# Sheet1.net
KiCad netlist of a schematic drawn in Altium Designer
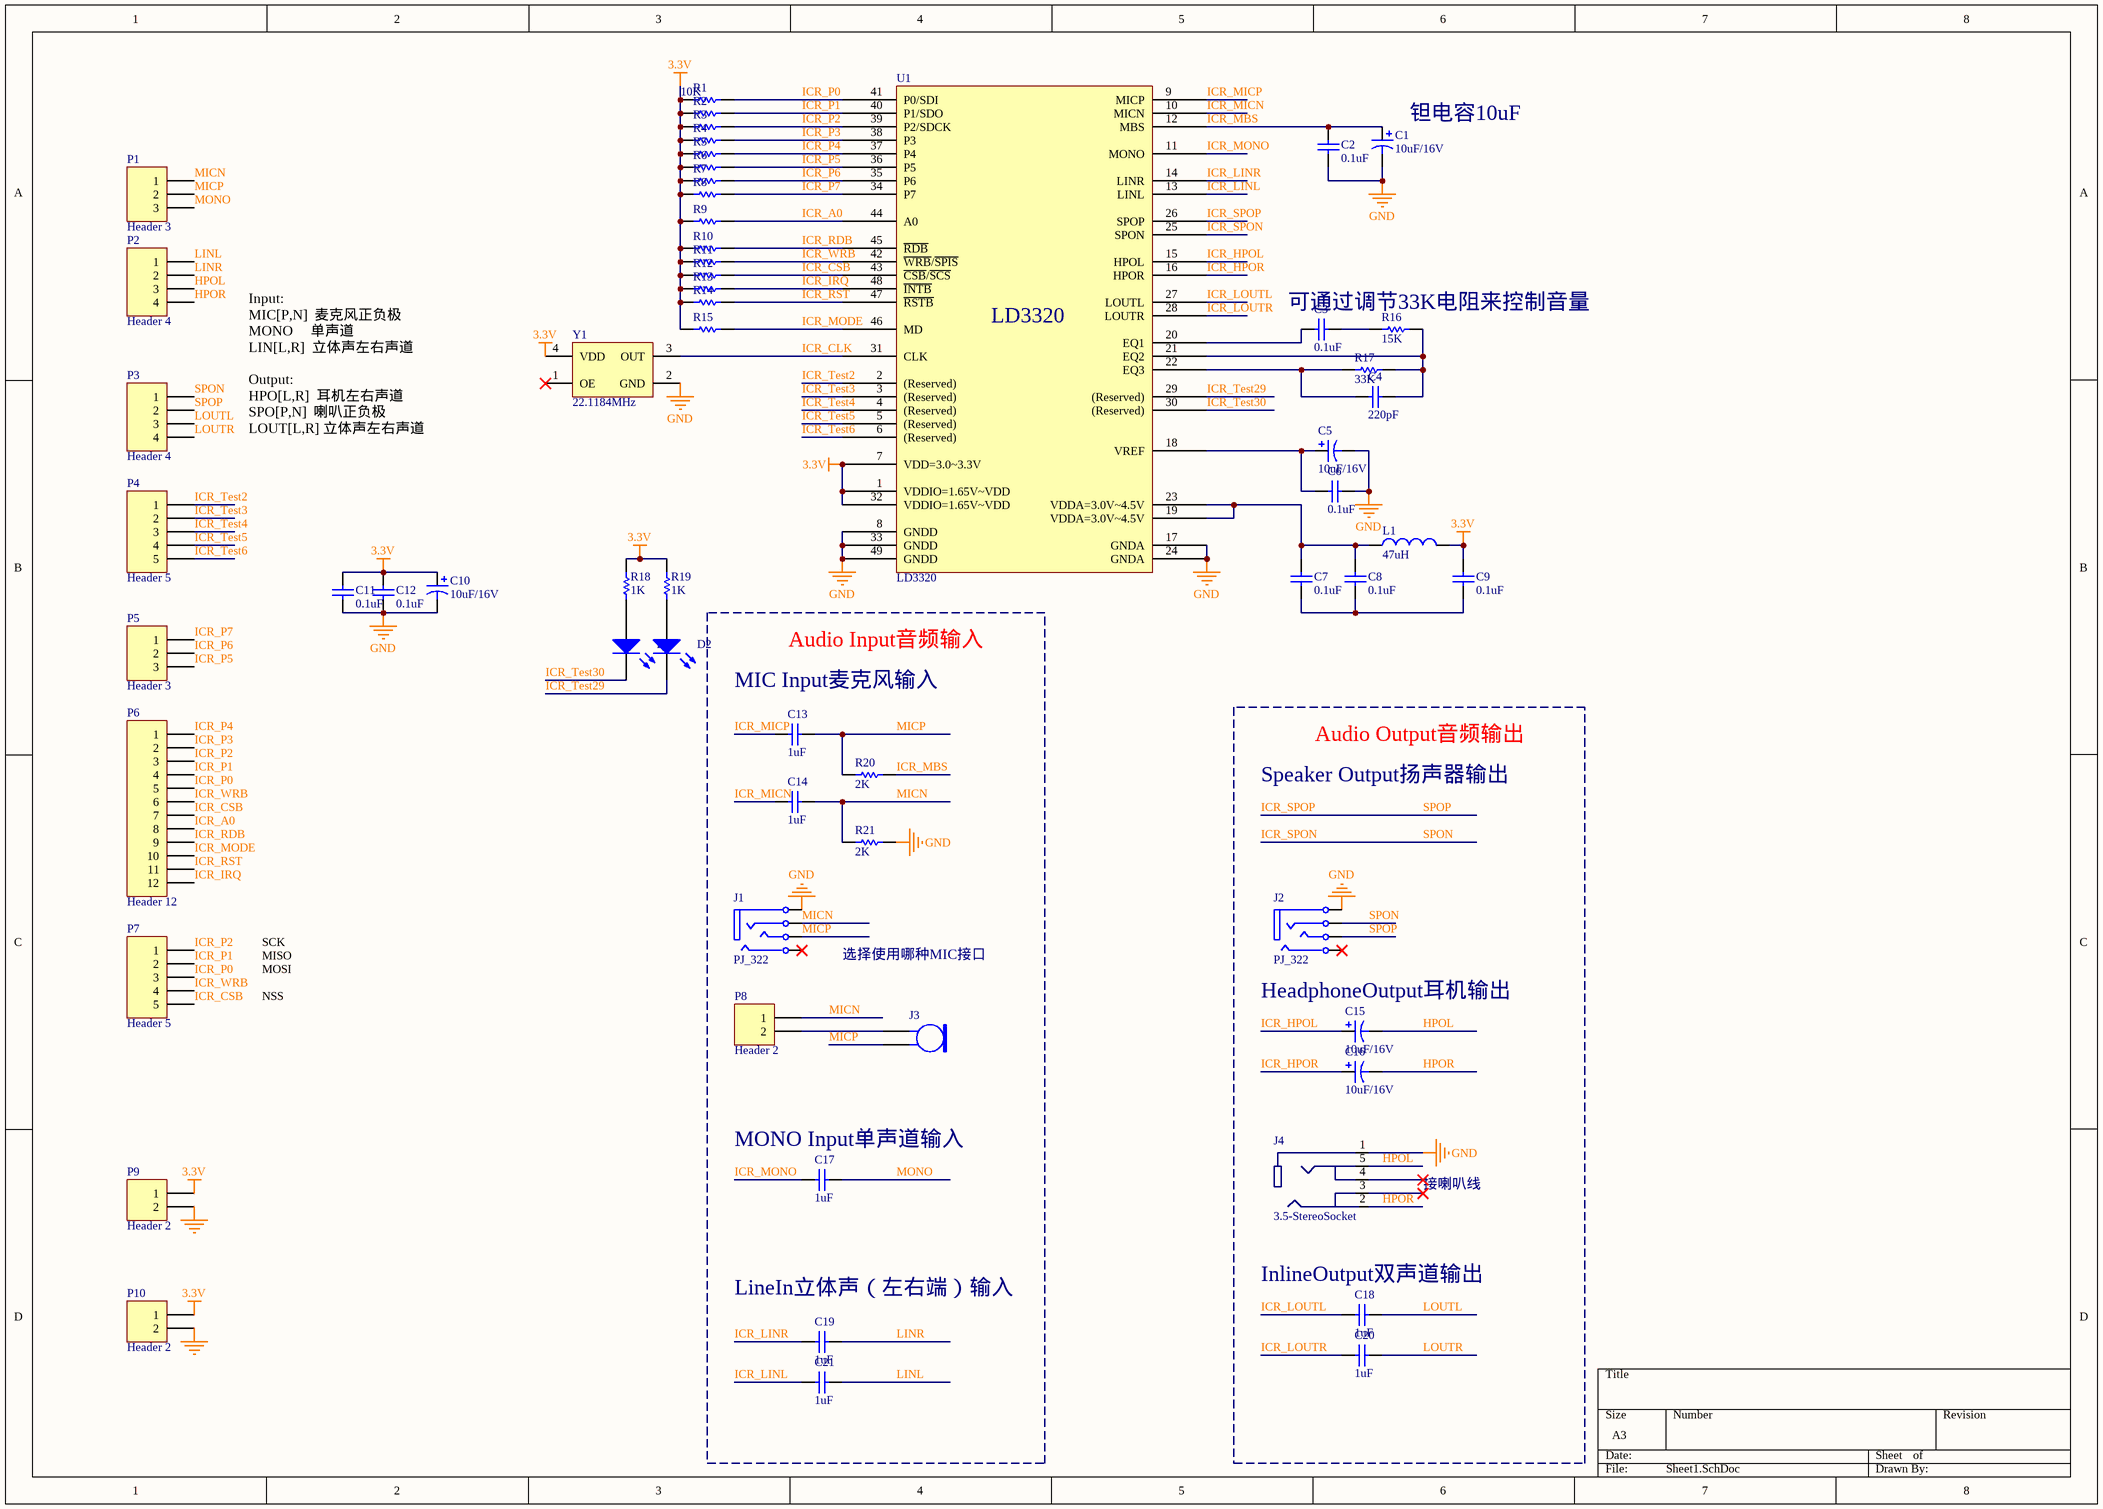
[diagram p0: Sheet1.SchDoc]

(export (version "E")
  (design (tool "Eeschema 10.0.6"))
  (components
    (comp (ref "C1")
      (value "10uF/16V")
      (footprint "1206")
      (description "Polarized Capacitor (Radial)")
      (fields (field (name "Comment") "Cap Pol1") (field (name "PUBLISHER") "Altium Limited"))
      (libsource (lib "Miscellaneous Devices") (part "Cap Pol1"))
    )
    (comp (ref "C2")
      (value "0.1uF")
      (footprint "0603")
      (description "Capacitor")
      (fields (field (name "Comment") "Cap") (field (name "PUBLISHER") "Altium Limited"))
      (libsource (lib "Miscellaneous Devices") (part "Cap"))
    )
    (comp (ref "C3")
      (value "0.1uF")
      (footprint "0603")
      (description "Capacitor")
      (fields (field (name "Comment") "Cap") (field (name "PUBLISHER") "Altium Limited"))
      (libsource (lib "Miscellaneous Devices") (part "Cap"))
    )
    (comp (ref "C4")
      (value "220pF")
      (footprint "0603")
      (description "Capacitor")
      (fields (field (name "Comment") "Cap") (field (name "PUBLISHER") "Altium Limited"))
      (libsource (lib "Miscellaneous Devices") (part "Cap"))
    )
    (comp (ref "C5")
      (value "10uF/16V")
      (footprint "1206")
      (description "Polarized Capacitor (Radial)")
      (fields (field (name "Comment") "Cap Pol1") (field (name "PUBLISHER") "Altium Limited"))
      (libsource (lib "Miscellaneous Devices") (part "Cap Pol1"))
    )
    (comp (ref "C6")
      (value "0.1uF")
      (footprint "0603")
      (description "Capacitor")
      (fields (field (name "Comment") "Cap") (field (name "PUBLISHER") "Altium Limited"))
      (libsource (lib "Miscellaneous Devices") (part "Cap"))
    )
    (comp (ref "C7")
      (value "0.1uF")
      (footprint "0603")
      (description "Capacitor")
      (fields (field (name "Comment") "Cap") (field (name "PUBLISHER") "Altium Limited"))
      (libsource (lib "Miscellaneous Devices") (part "Cap"))
    )
    (comp (ref "C8")
      (value "0.1uF")
      (footprint "0603")
      (description "Capacitor")
      (fields (field (name "Comment") "Cap") (field (name "PUBLISHER") "Altium Limited"))
      (libsource (lib "Miscellaneous Devices") (part "Cap"))
    )
    (comp (ref "C9")
      (value "0.1uF")
      (footprint "0603")
      (description "Capacitor")
      (fields (field (name "Comment") "Cap") (field (name "PUBLISHER") "Altium Limited"))
      (libsource (lib "Miscellaneous Devices") (part "Cap"))
    )
    (comp (ref "C10")
      (value "10uF/16V")
      (footprint "1206")
      (description "Polarized Capacitor (Radial)")
      (fields (field (name "Comment") "Cap Pol1") (field (name "PUBLISHER") "Altium Limited"))
      (libsource (lib "Miscellaneous Devices") (part "Cap Pol1"))
    )
    (comp (ref "C11")
      (value "0.1uF")
      (footprint "0603")
      (description "Capacitor")
      (fields (field (name "Comment") "Cap") (field (name "PUBLISHER") "Altium Limited"))
      (libsource (lib "Miscellaneous Devices") (part "Cap"))
    )
    (comp (ref "C12")
      (value "0.1uF")
      (footprint "0603")
      (description "Capacitor")
      (fields (field (name "Comment") "Cap") (field (name "PUBLISHER") "Altium Limited"))
      (libsource (lib "Miscellaneous Devices") (part "Cap"))
    )
    (comp (ref "C13")
      (value "1uF")
      (footprint "0603")
      (description "Capacitor")
      (fields (field (name "Comment") "Cap") (field (name "PUBLISHER") "Altium Limited"))
      (libsource (lib "Miscellaneous Devices") (part "Cap"))
    )
    (comp (ref "C14")
      (value "1uF")
      (footprint "0603")
      (description "Capacitor")
      (fields (field (name "Comment") "Cap") (field (name "PUBLISHER") "Altium Limited"))
      (libsource (lib "Miscellaneous Devices") (part "Cap"))
    )
    (comp (ref "C15")
      (value "10uF/16V")
      (footprint "1206")
      (description "Polarized Capacitor (Radial)")
      (fields (field (name "Comment") "Cap Pol1") (field (name "PUBLISHER") "Altium Limited"))
      (libsource (lib "Miscellaneous Devices") (part "Cap Pol1"))
    )
    (comp (ref "C16")
      (value "10uF/16V")
      (footprint "1206")
      (description "Polarized Capacitor (Radial)")
      (fields (field (name "Comment") "Cap Pol1") (field (name "PUBLISHER") "Altium Limited"))
      (libsource (lib "Miscellaneous Devices") (part "Cap Pol1"))
    )
    (comp (ref "C17")
      (value "1uF")
      (footprint "0603")
      (description "Capacitor")
      (fields (field (name "Comment") "Cap") (field (name "PUBLISHER") "Altium Limited"))
      (libsource (lib "Miscellaneous Devices") (part "Cap"))
    )
    (comp (ref "C18")
      (value "1uF")
      (footprint "0603")
      (description "Capacitor")
      (fields (field (name "Comment") "Cap") (field (name "PUBLISHER") "Altium Limited"))
      (libsource (lib "Miscellaneous Devices") (part "Cap"))
    )
    (comp (ref "C19")
      (value "1uF")
      (footprint "0603")
      (description "Capacitor")
      (fields (field (name "Comment") "Cap") (field (name "PUBLISHER") "Altium Limited"))
      (libsource (lib "Miscellaneous Devices") (part "Cap"))
    )
    (comp (ref "C20")
      (value "1uF")
      (footprint "0603")
      (description "Capacitor")
      (fields (field (name "Comment") "Cap") (field (name "PUBLISHER") "Altium Limited"))
      (libsource (lib "Miscellaneous Devices") (part "Cap"))
    )
    (comp (ref "C21")
      (value "1uF")
      (footprint "0603")
      (description "Capacitor")
      (fields (field (name "Comment") "Cap") (field (name "PUBLISHER") "Altium Limited"))
      (libsource (lib "Miscellaneous Devices") (part "Cap"))
    )
    (comp (ref "D1")
      (value "LED2")
      (footprint "0603-LED")
      (description "Typical RED, GREEN, YELLOW, AMBER GaAs LED")
      (fields (field (name "PUBLISHER") "Altium Limited"))
      (libsource (lib "Miscellaneous Devices") (part "LED2"))
    )
    (comp (ref "D2")
      (value "LED2")
      (footprint "0603-LED")
      (description "Typical RED, GREEN, YELLOW, AMBER GaAs LED")
      (fields (field (name "PUBLISHER") "Altium Limited"))
      (libsource (lib "Miscellaneous Devices") (part "LED2"))
    )
    (comp (ref "J1") (value "PJ_322") (footprint "PJ_322") (libsource (lib "Schlib1") (part "PJ_322")))
    (comp (ref "J2") (value "PJ_322") (footprint "PJ_322") (libsource (lib "Schlib1") (part "PJ_322")))
    (comp (ref "J3")
      (value "Mic2")
      (footprint "9*7mic")
      (description "Microphone")
      (fields (field (name "PUBLISHER") "Altium Limited"))
      (libsource (lib "Schlib1") (part "Mic2"))
    )
    (comp (ref "J4")
      (value "3.5-StereoSocket")
      (footprint "3F07")
      (description "AudioSocket")
      (libsource (lib "Schlib1") (part "3.5-StereoSocket"))
    )
    (comp (ref "L1")
      (value "47uH")
      (footprint "0805")
      (description "Inductor")
      (fields (field (name "PUBLISHER") "Altium Limited"))
      (libsource (lib "Miscellaneous Devices") (part "Inductor"))
    )
    (comp (ref "P1")
      (value "Header 3")
      (footprint "HDR1X3")
      (description "Header, 3-Pin")
      (fields (field (name "PUBLISHER") "Altium Limited"))
      (libsource (lib "Miscellaneous Connectors") (part "Header 3"))
    )
    (comp (ref "P2")
      (value "Header 4")
      (footprint "HDR1X4")
      (description "Header, 4-Pin")
      (fields (field (name "PUBLISHER") "Altium Limited"))
      (libsource (lib "Miscellaneous Connectors") (part "Header 4"))
    )
    (comp (ref "P3")
      (value "Header 4")
      (footprint "HDR1X4")
      (description "Header, 4-Pin")
      (fields (field (name "PUBLISHER") "Altium Limited"))
      (libsource (lib "Miscellaneous Connectors") (part "Header 4"))
    )
    (comp (ref "P4")
      (value "Header 5")
      (footprint "HDR1X5")
      (description "Header, 5-Pin")
      (fields (field (name "PUBLISHER") "Altium Limited"))
      (libsource (lib "Miscellaneous Connectors") (part "Header 5"))
    )
    (comp (ref "P5")
      (value "Header 3")
      (footprint "HDR1X3")
      (description "Header, 3-Pin")
      (fields (field (name "PUBLISHER") "Altium Limited"))
      (libsource (lib "Miscellaneous Connectors") (part "Header 3"))
    )
    (comp (ref "P6")
      (value "Header 12")
      (footprint "HDR1X12")
      (description "Header, 12-Pin")
      (fields (field (name "PUBLISHER") "Altium Limited"))
      (libsource (lib "Miscellaneous Connectors") (part "Header 12"))
    )
    (comp (ref "P7")
      (value "Header 5")
      (footprint "HDR1X5")
      (description "Header, 5-Pin")
      (fields (field (name "PUBLISHER") "Altium Limited"))
      (libsource (lib "Miscellaneous Connectors") (part "Header 5"))
    )
    (comp (ref "P8")
      (value "Header 2")
      (footprint "HDR1X2")
      (description "Header, 2-Pin")
      (fields (field (name "PUBLISHER") "Altium Limited"))
      (libsource (lib "Miscellaneous Connectors") (part "Header 2"))
    )
    (comp (ref "P9")
      (value "Header 2")
      (footprint "HDR1X2")
      (description "Header, 2-Pin")
      (fields (field (name "PUBLISHER") "Altium Limited"))
      (libsource (lib "Miscellaneous Connectors") (part "Header 2"))
    )
    (comp (ref "P10")
      (value "Header 2")
      (footprint "HDR1X2")
      (description "Header, 2-Pin")
      (fields (field (name "PUBLISHER") "Altium Limited"))
      (libsource (lib "Miscellaneous Connectors") (part "Header 2"))
    )
    (comp (ref "R1")
      (value "10K")
      (footprint "0603")
      (description "Resistor")
      (fields (field (name "Comment") "Res1") (field (name "PUBLISHER") "Altium Limited"))
      (libsource (lib "Miscellaneous Devices") (part "Res1"))
    )
    (comp (ref "R2")
      (value "Res1")
      (footprint "0603")
      (description "Resistor")
      (fields (field (name "PUBLISHER") "Altium Limited"))
      (libsource (lib "Miscellaneous Devices") (part "Res1"))
    )
    (comp (ref "R3")
      (value "Res1")
      (footprint "0603")
      (description "Resistor")
      (fields (field (name "PUBLISHER") "Altium Limited"))
      (libsource (lib "Miscellaneous Devices") (part "Res1"))
    )
    (comp (ref "R4")
      (value "Res1")
      (footprint "0603")
      (description "Resistor")
      (fields (field (name "PUBLISHER") "Altium Limited"))
      (libsource (lib "Miscellaneous Devices") (part "Res1"))
    )
    (comp (ref "R5")
      (value "Res1")
      (footprint "0603")
      (description "Resistor")
      (fields (field (name "PUBLISHER") "Altium Limited"))
      (libsource (lib "Miscellaneous Devices") (part "Res1"))
    )
    (comp (ref "R6")
      (value "Res1")
      (footprint "0603")
      (description "Resistor")
      (fields (field (name "PUBLISHER") "Altium Limited"))
      (libsource (lib "Miscellaneous Devices") (part "Res1"))
    )
    (comp (ref "R7")
      (value "Res1")
      (footprint "0603")
      (description "Resistor")
      (fields (field (name "PUBLISHER") "Altium Limited"))
      (libsource (lib "Miscellaneous Devices") (part "Res1"))
    )
    (comp (ref "R8")
      (value "Res1")
      (footprint "0603")
      (description "Resistor")
      (fields (field (name "PUBLISHER") "Altium Limited"))
      (libsource (lib "Miscellaneous Devices") (part "Res1"))
    )
    (comp (ref "R9")
      (value "Res1")
      (footprint "0603")
      (description "Resistor")
      (fields (field (name "PUBLISHER") "Altium Limited"))
      (libsource (lib "Miscellaneous Devices") (part "Res1"))
    )
    (comp (ref "R10")
      (value "Res1")
      (footprint "0603")
      (description "Resistor")
      (fields (field (name "PUBLISHER") "Altium Limited"))
      (libsource (lib "Miscellaneous Devices") (part "Res1"))
    )
    (comp (ref "R11")
      (value "Res1")
      (footprint "0603")
      (description "Resistor")
      (fields (field (name "PUBLISHER") "Altium Limited"))
      (libsource (lib "Miscellaneous Devices") (part "Res1"))
    )
    (comp (ref "R12")
      (value "Res1")
      (footprint "0603")
      (description "Resistor")
      (fields (field (name "PUBLISHER") "Altium Limited"))
      (libsource (lib "Miscellaneous Devices") (part "Res1"))
    )
    (comp (ref "R13")
      (value "Res1")
      (footprint "0603")
      (description "Resistor")
      (fields (field (name "PUBLISHER") "Altium Limited"))
      (libsource (lib "Miscellaneous Devices") (part "Res1"))
    )
    (comp (ref "R14")
      (value "Res1")
      (footprint "0603")
      (description "Resistor")
      (fields (field (name "PUBLISHER") "Altium Limited"))
      (libsource (lib "Miscellaneous Devices") (part "Res1"))
    )
    (comp (ref "R15")
      (value "Res1")
      (footprint "0603")
      (description "Resistor")
      (fields (field (name "PUBLISHER") "Altium Limited"))
      (libsource (lib "Miscellaneous Devices") (part "Res1"))
    )
    (comp (ref "R16")
      (value "15K")
      (footprint "0603")
      (description "Resistor")
      (fields (field (name "Comment") "Res1") (field (name "PUBLISHER") "Altium Limited"))
      (libsource (lib "Miscellaneous Devices") (part "Res1"))
    )
    (comp (ref "R17")
      (value "33K")
      (footprint "0603")
      (description "Resistor")
      (fields (field (name "Comment") "Res1") (field (name "PUBLISHER") "Altium Limited"))
      (libsource (lib "Miscellaneous Devices") (part "Res1"))
    )
    (comp (ref "R18")
      (value "1K")
      (footprint "0603")
      (description "Resistor")
      (fields (field (name "Comment") "Res1") (field (name "PUBLISHER") "Altium Limited"))
      (libsource (lib "Miscellaneous Devices") (part "Res1"))
    )
    (comp (ref "R19")
      (value "1K")
      (footprint "0603")
      (description "Resistor")
      (fields (field (name "Comment") "Res1") (field (name "PUBLISHER") "Altium Limited"))
      (libsource (lib "Miscellaneous Devices") (part "Res1"))
    )
    (comp (ref "R20")
      (value "2K")
      (footprint "0603")
      (description "Resistor")
      (fields (field (name "Comment") "Res1") (field (name "PUBLISHER") "Altium Limited"))
      (libsource (lib "Miscellaneous Devices") (part "Res1"))
    )
    (comp (ref "R21")
      (value "2K")
      (footprint "0603")
      (description "Resistor")
      (fields (field (name "Comment") "Res1") (field (name "PUBLISHER") "Altium Limited"))
      (libsource (lib "Miscellaneous Devices") (part "Res1"))
    )
    (comp (ref "U1")
      (value "LD3320")
      (footprint "QFN-48P")
      (description "SpeechRecognition")
      (libsource (lib "Schlib1") (part "LD3320"))
    )
    (comp (ref "Y1")
      (value "22.1184MHz")
      (footprint "5*3.2")
      (description "oscillator")
      (libsource (lib "Schlib1") (part "SPXO"))
    )
  )
  (nets
    (net (code "1") (name "/HPOL") (class "Default")
      (node (ref "C15") (pin "2") (pinfunction "2_2") (pintype "passive"))
      (node (ref "J4") (pin "5") (pinfunction "5_5") (pintype "passive"))
      (node (ref "P2") (pin "3") (pinfunction "3_3") (pintype "passive"))
    )
    (net (code "2") (name "/HPOR") (class "Default")
      (node (ref "C16") (pin "2") (pinfunction "2_2") (pintype "passive"))
      (node (ref "J4") (pin "2") (pinfunction "2_2") (pintype "passive"))
      (node (ref "P2") (pin "4") (pinfunction "4_4") (pintype "passive"))
    )
    (net (code "3") (name "/ICR_A0") (class "Default")
      (node (ref "P6") (pin "8") (pinfunction "8_8") (pintype "passive"))
      (node (ref "R9") (pin "1") (pinfunction "1_1") (pintype "passive"))
      (node (ref "U1") (pin "44") (pinfunction "A0_44") (pintype "passive"))
    )
    (net (code "4") (name "/ICR_CLK") (class "Default")
      (node (ref "U1") (pin "31") (pinfunction "CLK_31") (pintype "passive"))
      (node (ref "Y1") (pin "3") (pinfunction "OUT_3") (pintype "passive"))
    )
    (net (code "5") (name "/ICR_CSB") (class "Default")
      (node (ref "P6") (pin "7") (pinfunction "7_7") (pintype "passive"))
      (node (ref "P7") (pin "5") (pinfunction "5_5") (pintype "passive"))
      (node (ref "R12") (pin "1") (pinfunction "1_1") (pintype "passive"))
      (node (ref "U1") (pin "43") (pinfunction "~{CSB}/~{SCS}_43") (pintype "passive"))
    )
    (net (code "6") (name "/ICR_HPOL") (class "Default")
      (node (ref "C15") (pin "1") (pinfunction "1_1") (pintype "passive"))
      (node (ref "U1") (pin "15") (pinfunction "HPOL_15") (pintype "passive"))
    )
    (net (code "7") (name "/ICR_HPOR") (class "Default")
      (node (ref "C16") (pin "1") (pinfunction "1_1") (pintype "passive"))
      (node (ref "U1") (pin "16") (pinfunction "HPOR_16") (pintype "passive"))
    )
    (net (code "8") (name "/ICR_IRQ") (class "Default")
      (node (ref "P6") (pin "12") (pinfunction "12_12") (pintype "passive"))
      (node (ref "R13") (pin "1") (pinfunction "1_1") (pintype "passive"))
      (node (ref "U1") (pin "48") (pinfunction "~{INTB}_48") (pintype "passive"))
    )
    (net (code "9") (name "/ICR_LINL") (class "Default")
      (node (ref "C21") (pin "1") (pinfunction "1_1") (pintype "passive"))
      (node (ref "U1") (pin "13") (pinfunction "LINL_13") (pintype "passive"))
    )
    (net (code "10") (name "/ICR_LINR") (class "Default")
      (node (ref "C19") (pin "1") (pinfunction "1_1") (pintype "passive"))
      (node (ref "U1") (pin "14") (pinfunction "LINR_14") (pintype "passive"))
    )
    (net (code "11") (name "/ICR_LOUTL") (class "Default")
      (node (ref "C18") (pin "1") (pinfunction "1_1") (pintype "passive"))
      (node (ref "U1") (pin "27") (pinfunction "LOUTL_27") (pintype "passive"))
    )
    (net (code "12") (name "/ICR_LOUTR") (class "Default")
      (node (ref "C20") (pin "1") (pinfunction "1_1") (pintype "passive"))
      (node (ref "U1") (pin "28") (pinfunction "LOUTR_28") (pintype "passive"))
    )
    (net (code "13") (name "/ICR_MBS") (class "Default")
      (node (ref "C1") (pin "1") (pinfunction "1_1") (pintype "passive"))
      (node (ref "C2") (pin "2") (pinfunction "2_2") (pintype "passive"))
      (node (ref "R20") (pin "2") (pinfunction "2_2") (pintype "passive"))
      (node (ref "U1") (pin "12") (pinfunction "MBS_12") (pintype "passive"))
    )
    (net (code "14") (name "/ICR_MICN") (class "Default")
      (node (ref "C14") (pin "1") (pinfunction "1_1") (pintype "passive"))
      (node (ref "U1") (pin "10") (pinfunction "MICN_10") (pintype "passive"))
    )
    (net (code "15") (name "/ICR_MICP") (class "Default")
      (node (ref "C13") (pin "1") (pinfunction "1_1") (pintype "passive"))
      (node (ref "U1") (pin "9") (pinfunction "MICP_9") (pintype "passive"))
    )
    (net (code "16") (name "/ICR_MODE") (class "Default")
      (node (ref "P6") (pin "10") (pinfunction "10_10") (pintype "passive"))
      (node (ref "R15") (pin "1") (pinfunction "1_1") (pintype "passive"))
      (node (ref "U1") (pin "46") (pinfunction "MD_46") (pintype "passive"))
    )
    (net (code "17") (name "/ICR_MONO") (class "Default")
      (node (ref "C17") (pin "1") (pinfunction "1_1") (pintype "passive"))
      (node (ref "U1") (pin "11") (pinfunction "MONO_11") (pintype "passive"))
    )
    (net (code "18") (name "/ICR_P0") (class "Default")
      (node (ref "P6") (pin "5") (pinfunction "5_5") (pintype "passive"))
      (node (ref "P7") (pin "3") (pinfunction "3_3") (pintype "passive"))
      (node (ref "R1") (pin "1") (pinfunction "1_1") (pintype "passive"))
      (node (ref "U1") (pin "41") (pinfunction "P0/SDI_41") (pintype "passive"))
    )
    (net (code "19") (name "/ICR_P1") (class "Default")
      (node (ref "P6") (pin "4") (pinfunction "4_4") (pintype "passive"))
      (node (ref "P7") (pin "2") (pinfunction "2_2") (pintype "passive"))
      (node (ref "R2") (pin "1") (pinfunction "1_1") (pintype "passive"))
      (node (ref "U1") (pin "40") (pinfunction "P1/SDO_40") (pintype "passive"))
    )
    (net (code "20") (name "/ICR_P2") (class "Default")
      (node (ref "P6") (pin "3") (pinfunction "3_3") (pintype "passive"))
      (node (ref "P7") (pin "1") (pinfunction "1_1") (pintype "passive"))
      (node (ref "R3") (pin "1") (pinfunction "1_1") (pintype "passive"))
      (node (ref "U1") (pin "39") (pinfunction "P2/SDCK_39") (pintype "passive"))
    )
    (net (code "21") (name "/ICR_P3") (class "Default")
      (node (ref "P6") (pin "2") (pinfunction "2_2") (pintype "passive"))
      (node (ref "R4") (pin "1") (pinfunction "1_1") (pintype "passive"))
      (node (ref "U1") (pin "38") (pinfunction "P3_38") (pintype "passive"))
    )
    (net (code "22") (name "/ICR_P4") (class "Default")
      (node (ref "P6") (pin "1") (pinfunction "1_1") (pintype "passive"))
      (node (ref "R5") (pin "1") (pinfunction "1_1") (pintype "passive"))
      (node (ref "U1") (pin "37") (pinfunction "P4_37") (pintype "passive"))
    )
    (net (code "23") (name "/ICR_P5") (class "Default")
      (node (ref "P5") (pin "3") (pinfunction "3_3") (pintype "passive"))
      (node (ref "R6") (pin "1") (pinfunction "1_1") (pintype "passive"))
      (node (ref "U1") (pin "36") (pinfunction "P5_36") (pintype "passive"))
    )
    (net (code "24") (name "/ICR_P6") (class "Default")
      (node (ref "P5") (pin "2") (pinfunction "2_2") (pintype "passive"))
      (node (ref "R7") (pin "1") (pinfunction "1_1") (pintype "passive"))
      (node (ref "U1") (pin "35") (pinfunction "P6_35") (pintype "passive"))
    )
    (net (code "25") (name "/ICR_P7") (class "Default")
      (node (ref "P5") (pin "1") (pinfunction "1_1") (pintype "passive"))
      (node (ref "R8") (pin "1") (pinfunction "1_1") (pintype "passive"))
      (node (ref "U1") (pin "34") (pinfunction "P7_34") (pintype "passive"))
    )
    (net (code "26") (name "/ICR_RDB") (class "Default")
      (node (ref "P6") (pin "9") (pinfunction "9_9") (pintype "passive"))
      (node (ref "R10") (pin "1") (pinfunction "1_1") (pintype "passive"))
      (node (ref "U1") (pin "45") (pinfunction "~{RDB}_45") (pintype "passive"))
    )
    (net (code "27") (name "/ICR_RST") (class "Default")
      (node (ref "P6") (pin "11") (pinfunction "11_11") (pintype "passive"))
      (node (ref "R14") (pin "1") (pinfunction "1_1") (pintype "passive"))
      (node (ref "U1") (pin "47") (pinfunction "~{RSTB}_47") (pintype "passive"))
    )
    (net (code "28") (name "/ICR_SPON") (class "Default")
      (node (ref "J2") (pin "2") (pinfunction "R_2") (pintype "passive"))
      (node (ref "P3") (pin "1") (pinfunction "1_1") (pintype "passive"))
      (node (ref "U1") (pin "25") (pinfunction "SPON_25") (pintype "passive"))
    )
    (net (code "29") (name "/ICR_SPOP") (class "Default")
      (node (ref "J2") (pin "3") (pinfunction "T_3") (pintype "passive"))
      (node (ref "P3") (pin "2") (pinfunction "2_2") (pintype "passive"))
      (node (ref "U1") (pin "26") (pinfunction "SPOP_26") (pintype "passive"))
    )
    (net (code "30") (name "/ICR_Test2") (class "Default")
      (node (ref "P4") (pin "1") (pinfunction "1_1") (pintype "passive"))
      (node (ref "U1") (pin "2") (pinfunction "(Reserved)_2") (pintype "passive"))
    )
    (net (code "31") (name "/ICR_Test3") (class "Default")
      (node (ref "P4") (pin "2") (pinfunction "2_2") (pintype "passive"))
      (node (ref "U1") (pin "3") (pinfunction "(Reserved)_3") (pintype "passive"))
    )
    (net (code "32") (name "/ICR_Test4") (class "Default")
      (node (ref "P4") (pin "3") (pinfunction "3_3") (pintype "passive"))
      (node (ref "U1") (pin "4") (pinfunction "(Reserved)_4") (pintype "passive"))
    )
    (net (code "33") (name "/ICR_Test5") (class "Default")
      (node (ref "P4") (pin "4") (pinfunction "4_4") (pintype "passive"))
      (node (ref "U1") (pin "5") (pinfunction "(Reserved)_5") (pintype "passive"))
    )
    (net (code "34") (name "/ICR_Test6") (class "Default")
      (node (ref "P4") (pin "5") (pinfunction "5_5") (pintype "passive"))
      (node (ref "U1") (pin "6") (pinfunction "(Reserved)_6") (pintype "passive"))
    )
    (net (code "35") (name "/ICR_Test29") (class "Default")
      (node (ref "D2") (pin "2") (pinfunction "K_2") (pintype "passive"))
      (node (ref "U1") (pin "29") (pinfunction "(Reserved)_29") (pintype "passive"))
    )
    (net (code "36") (name "/ICR_Test30") (class "Default")
      (node (ref "D1") (pin "2") (pinfunction "K_2") (pintype "passive"))
      (node (ref "U1") (pin "30") (pinfunction "(Reserved)_30") (pintype "passive"))
    )
    (net (code "37") (name "/ICR_WRB") (class "Default")
      (node (ref "P6") (pin "6") (pinfunction "6_6") (pintype "passive"))
      (node (ref "P7") (pin "4") (pinfunction "4_4") (pintype "passive"))
      (node (ref "R11") (pin "1") (pinfunction "1_1") (pintype "passive"))
      (node (ref "U1") (pin "42") (pinfunction "~{WRB}/~{SPIS}_42") (pintype "passive"))
    )
    (net (code "38") (name "/LINL") (class "Default")
      (node (ref "C21") (pin "2") (pinfunction "2_2") (pintype "passive"))
      (node (ref "P2") (pin "1") (pinfunction "1_1") (pintype "passive"))
    )
    (net (code "39") (name "/LINR") (class "Default")
      (node (ref "C19") (pin "2") (pinfunction "2_2") (pintype "passive"))
      (node (ref "P2") (pin "2") (pinfunction "2_2") (pintype "passive"))
    )
    (net (code "40") (name "/LOUTL") (class "Default")
      (node (ref "C18") (pin "2") (pinfunction "2_2") (pintype "passive"))
      (node (ref "P3") (pin "3") (pinfunction "3_3") (pintype "passive"))
    )
    (net (code "41") (name "/LOUTR") (class "Default")
      (node (ref "C20") (pin "2") (pinfunction "2_2") (pintype "passive"))
      (node (ref "P3") (pin "4") (pinfunction "4_4") (pintype "passive"))
    )
    (net (code "42") (name "/MICN") (class "Default")
      (node (ref "C14") (pin "2") (pinfunction "2_2") (pintype "passive"))
      (node (ref "J1") (pin "2") (pinfunction "R_2") (pintype "passive"))
      (node (ref "P1") (pin "1") (pinfunction "1_1") (pintype "passive"))
      (node (ref "P8") (pin "1") (pinfunction "1_1") (pintype "passive"))
      (node (ref "R21") (pin "1") (pinfunction "1_1") (pintype "passive"))
    )
    (net (code "43") (name "/MICP") (class "Default")
      (node (ref "C13") (pin "2") (pinfunction "2_2") (pintype "passive"))
      (node (ref "J1") (pin "3") (pinfunction "T_3") (pintype "passive"))
      (node (ref "J3") (pin "2") (pinfunction "2_2") (pintype "passive"))
      (node (ref "P1") (pin "2") (pinfunction "2_2") (pintype "passive"))
      (node (ref "R20") (pin "1") (pinfunction "1_1") (pintype "passive"))
    )
    (net (code "44") (name "/MONO") (class "Default")
      (node (ref "C17") (pin "2") (pinfunction "2_2") (pintype "passive"))
      (node (ref "P1") (pin "3") (pinfunction "3_3") (pintype "passive"))
    )
    (net (code "45") (name "3.3V") (class "Default")
      (node (ref "C10") (pin "1") (pinfunction "1_1") (pintype "passive"))
      (node (ref "C11") (pin "2") (pinfunction "2_2") (pintype "passive"))
      (node (ref "C12") (pin "2") (pinfunction "2_2") (pintype "passive"))
      (node (ref "C9") (pin "1") (pinfunction "1_1") (pintype "passive"))
      (node (ref "L1") (pin "2") (pinfunction "2_2") (pintype "passive"))
      (node (ref "P10") (pin "1") (pinfunction "1_1") (pintype "passive"))
      (node (ref "P9") (pin "1") (pinfunction "1_1") (pintype "passive"))
      (node (ref "R1") (pin "2") (pinfunction "2_2") (pintype "passive"))
      (node (ref "R10") (pin "2") (pinfunction "2_2") (pintype "passive"))
      (node (ref "R11") (pin "2") (pinfunction "2_2") (pintype "passive"))
      (node (ref "R12") (pin "2") (pinfunction "2_2") (pintype "passive"))
      (node (ref "R13") (pin "2") (pinfunction "2_2") (pintype "passive"))
      (node (ref "R14") (pin "2") (pinfunction "2_2") (pintype "passive"))
      (node (ref "R15") (pin "2") (pinfunction "2_2") (pintype "passive"))
      (node (ref "R18") (pin "2") (pinfunction "2_2") (pintype "passive"))
      (node (ref "R19") (pin "2") (pinfunction "2_2") (pintype "passive"))
      (node (ref "R2") (pin "2") (pinfunction "2_2") (pintype "passive"))
      (node (ref "R3") (pin "2") (pinfunction "2_2") (pintype "passive"))
      (node (ref "R4") (pin "2") (pinfunction "2_2") (pintype "passive"))
      (node (ref "R5") (pin "2") (pinfunction "2_2") (pintype "passive"))
      (node (ref "R6") (pin "2") (pinfunction "2_2") (pintype "passive"))
      (node (ref "R7") (pin "2") (pinfunction "2_2") (pintype "passive"))
      (node (ref "R8") (pin "2") (pinfunction "2_2") (pintype "passive"))
      (node (ref "R9") (pin "2") (pinfunction "2_2") (pintype "passive"))
      (node (ref "U1") (pin "1") (pinfunction "VDDIO=1.65V~VDD_1") (pintype "power_in"))
      (node (ref "U1") (pin "32") (pinfunction "VDDIO=1.65V~VDD_32") (pintype "passive"))
      (node (ref "U1") (pin "7") (pinfunction "VDD=3.0~3.3V_7") (pintype "power_in"))
      (node (ref "Y1") (pin "4") (pinfunction "VDD_4") (pintype "passive"))
    )
    (net (code "46") (name "GND") (class "Default")
      (node (ref "C1") (pin "2") (pinfunction "2_2") (pintype "passive"))
      (node (ref "C10") (pin "2") (pinfunction "2_2") (pintype "passive"))
      (node (ref "C11") (pin "1") (pinfunction "1_1") (pintype "passive"))
      (node (ref "C12") (pin "1") (pinfunction "1_1") (pintype "passive"))
      (node (ref "C2") (pin "1") (pinfunction "1_1") (pintype "passive"))
      (node (ref "C5") (pin "2") (pinfunction "2_2") (pintype "passive"))
      (node (ref "C6") (pin "1") (pinfunction "1_1") (pintype "passive"))
      (node (ref "J1") (pin "1") (pinfunction "S_1") (pintype "power_in"))
      (node (ref "J2") (pin "1") (pinfunction "S_1") (pintype "power_in"))
      (node (ref "J4") (pin "1") (pinfunction "GND_1") (pintype "passive"))
      (node (ref "P10") (pin "2") (pinfunction "2_2") (pintype "passive"))
      (node (ref "P9") (pin "2") (pinfunction "2_2") (pintype "passive"))
      (node (ref "R21") (pin "2") (pinfunction "2_2") (pintype "passive"))
      (node (ref "U1") (pin "17") (pinfunction "GNDA_17") (pintype "passive"))
      (node (ref "U1") (pin "24") (pinfunction "GNDA_24") (pintype "passive"))
      (node (ref "U1") (pin "33") (pinfunction "GNDD_33") (pintype "passive"))
      (node (ref "U1") (pin "49") (pinfunction "GNDD_49") (pintype "passive"))
      (node (ref "U1") (pin "8") (pinfunction "GNDD_8") (pintype "power_in"))
      (node (ref "Y1") (pin "2") (pinfunction "GND_2") (pintype "passive"))
    )
    (net (code "47") (name "Net-(C3-Pad1)") (class "Default")
      (node (ref "C3") (pin "1") (pinfunction "1_1") (pintype "passive"))
      (node (ref "R16") (pin "1") (pinfunction "1_1") (pintype "passive"))
    )
    (net (code "48") (name "Net-(C7-Pad1)") (class "Default")
      (node (ref "C7") (pin "1") (pinfunction "1_1") (pintype "passive"))
      (node (ref "C8") (pin "1") (pinfunction "1_1") (pintype "passive"))
      (node (ref "L1") (pin "1") (pinfunction "1_1") (pintype "passive"))
      (node (ref "U1") (pin "19") (pinfunction "VDDA=3.0V~4.5V_19") (pintype "passive"))
      (node (ref "U1") (pin "23") (pinfunction "VDDA=3.0V~4.5V_23") (pintype "passive"))
    )
    (net (code "49") (name "Net-(C7-Pad2)") (class "Default")
      (node (ref "C7") (pin "2") (pinfunction "2_2") (pintype "passive"))
      (node (ref "C8") (pin "2") (pinfunction "2_2") (pintype "passive"))
      (node (ref "C9") (pin "2") (pinfunction "2_2") (pintype "passive"))
    )
    (net (code "50") (name "Net-(D1-A)") (class "Default")
      (node (ref "D1") (pin "1") (pinfunction "A_1") (pintype "passive"))
      (node (ref "R18") (pin "1") (pinfunction "1_1") (pintype "passive"))
    )
    (net (code "51") (name "Net-(D2-A)") (class "Default")
      (node (ref "D2") (pin "1") (pinfunction "A_1") (pintype "passive"))
      (node (ref "R19") (pin "1") (pinfunction "1_1") (pintype "passive"))
    )
    (net (code "52") (name "Net-(J3-Pad1)") (class "Default")
      (node (ref "J3") (pin "1") (pinfunction "1_1") (pintype "passive"))
      (node (ref "P8") (pin "2") (pinfunction "2_2") (pintype "passive"))
    )
    (net (code "53") (name "Net-(U1-EQ1)") (class "Default")
      (node (ref "C3") (pin "2") (pinfunction "2_2") (pintype "passive"))
      (node (ref "U1") (pin "20") (pinfunction "EQ1_20") (pintype "passive"))
    )
    (net (code "54") (name "Net-(U1-EQ2)") (class "Default")
      (node (ref "C4") (pin "1") (pinfunction "1_1") (pintype "passive"))
      (node (ref "R16") (pin "2") (pinfunction "2_2") (pintype "passive"))
      (node (ref "R17") (pin "2") (pinfunction "2_2") (pintype "passive"))
      (node (ref "U1") (pin "21") (pinfunction "EQ2_21") (pintype "passive"))
    )
    (net (code "55") (name "Net-(U1-EQ3)") (class "Default")
      (node (ref "C4") (pin "2") (pinfunction "2_2") (pintype "passive"))
      (node (ref "R17") (pin "1") (pinfunction "1_1") (pintype "passive"))
      (node (ref "U1") (pin "22") (pinfunction "EQ3_22") (pintype "passive"))
    )
    (net (code "56") (name "Net-(U1-VREF)") (class "Default")
      (node (ref "C5") (pin "1") (pinfunction "1_1") (pintype "passive"))
      (node (ref "C6") (pin "2") (pinfunction "2_2") (pintype "passive"))
      (node (ref "U1") (pin "18") (pinfunction "VREF_18") (pintype "passive"))
    )
    (net (code "57") (name "unconnected-(J1-T-Pad4)") (class "Default")
      (node (ref "J1") (pin "4") (pinfunction "T_4") (pintype "passive+no_connect"))
    )
    (net (code "58") (name "unconnected-(J2-T-Pad4)") (class "Default")
      (node (ref "J2") (pin "4") (pinfunction "T_4") (pintype "passive+no_connect"))
    )
    (net (code "59") (name "unconnected-(J4-Pad3)") (class "Default")
      (node (ref "J4") (pin "3") (pinfunction "3_3") (pintype "passive+no_connect"))
    )
    (net (code "60") (name "unconnected-(J4-Pad4)") (class "Default")
      (node (ref "J4") (pin "4") (pinfunction "4_4") (pintype "passive+no_connect"))
    )
    (net (code "61") (name "unconnected-(Y1-OE-Pad1)") (class "Default")
      (node (ref "Y1") (pin "1") (pinfunction "OE_1") (pintype "passive+no_connect"))
    )
  )
)
